# Button.net
KiCad netlist of a schematic drawn in Altium Designer
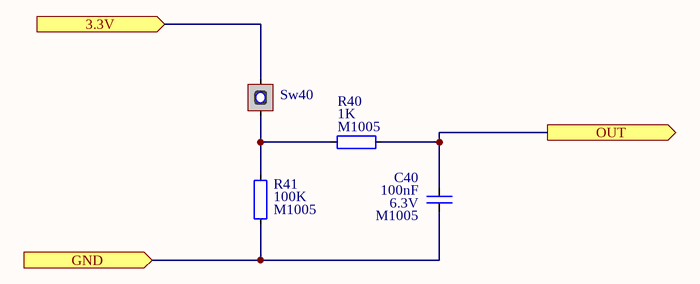
[diagram p0: Button.SchDoc]

(export (version "E")
  (design (tool "Eeschema 10.0.6"))
  (components
    (comp (ref "C40")
      (value "100nF")
      (footprint "Capacitor_Ceramic_M1005_I0402")
      (description "Cap, Cer, 100nF, 6.3V, M1005")
      (fields
        (field (name "VOLTAGE") "6.3V")
        (field (name "MANUFACTURER PART NUMBER") "04026D104KAT4A")
        (field (name "MANUFACTURER") "Kyocera")
        (field (name "PACKAGE") "M1005")
      )
      (libsource (lib "Capacitor") (part "Capacitor_Ceramic"))
    )
    (comp (ref "R40")
      (value "1K")
      (footprint "Resistor_Smd_M1005_I0402")
      (description "Res, 1K, 1%, M1005")
      (fields
        (field (name "TOLERANCE") "1%")
        (field (name "MANUFACTURER") "Yageo")
        (field (name "PACKAGE") "M1005")
      )
      (libsource (lib "Resistor") (part "Resistor"))
    )
    (comp (ref "R41")
      (value "100K")
      (footprint "Resistor_Smd_M1005_I0402")
      (description "Res, 100K, 1%, M1005")
      (fields
        (field (name "TOLERANCE") "1%")
        (field (name "MANUFACTURER") "Yageo")
        (field (name "PACKAGE") "M1005")
      )
      (libsource (lib "Resistor") (part "Resistor"))
    )
    (comp (ref "Sw40")
      (value "Tactile, SPST")
      (footprint "Tactile, SPST - Panasonic, EVQQ2")
      (libsource (lib "Switch") (part "Tactile, SPST"))
    )
  )
  (nets
    (net (code "1") (name "/3.3V") (class "Default")
      (node (ref "Sw40") (pin "A") (pinfunction "A_A") (pintype "passive"))
    )
    (net (code "2") (name "/GND") (class "Default")
      (node (ref "C40") (pin "2") (pinfunction "2_2") (pintype "passive"))
      (node (ref "R41") (pin "2") (pinfunction "2_2") (pintype "passive"))
    )
    (net (code "3") (name "/OUT") (class "Default")
      (node (ref "C40") (pin "1") (pinfunction "1_1") (pintype "passive"))
      (node (ref "R40") (pin "2") (pinfunction "2_2") (pintype "passive"))
    )
    (net (code "4") (name "Net-(R40-Pad1)") (class "Default")
      (node (ref "R40") (pin "1") (pinfunction "1_1") (pintype "passive"))
      (node (ref "R41") (pin "1") (pinfunction "1_1") (pintype "passive"))
      (node (ref "Sw40") (pin "B") (pinfunction "B_B") (pintype "passive"))
    )
  )
)
